# series_parallel_examples4.net
KiCad netlist of a schematic drawn in EAGLE
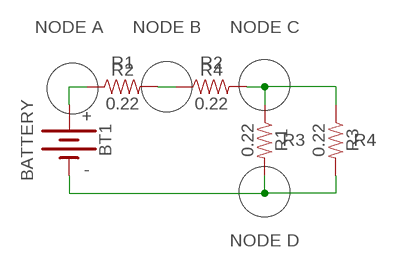
[diagram p0: schematic, sheet 1]

(export (version "E")
  (design (tool "Eeschema 10.0.6"))
  (components
    (comp (ref "BT1")
      (value "BATTERY-9V")
      (footprint "eagle-import:BATTCON_9V")
      (libsource (lib "eagle-import") (part "BATTERY-9V"))
    )
    (comp (ref "R1")
      (value "0.22")
      (footprint "eagle-import:0805")
      (libsource (lib "eagle-import") (part "0.22OHM-0805-1/4W-1%"))
    )
    (comp (ref "R2")
      (value "0.22")
      (footprint "eagle-import:0805")
      (libsource (lib "eagle-import") (part "0.22OHM-0805-1/4W-1%"))
    )
    (comp (ref "R3")
      (value "0.22")
      (footprint "eagle-import:0805")
      (libsource (lib "eagle-import") (part "0.22OHM-0805-1/4W-1%"))
    )
    (comp (ref "R4")
      (value "0.22")
      (footprint "eagle-import:0805")
      (libsource (lib "eagle-import") (part "0.22OHM-0805-1/4W-1%"))
    )
  )
  (nets
    (net (code "1") (name "Net-(BT1-Pad+)") (class "Default")
      (node (ref "BT1") (pin "+") (pinfunction "+_+") (pintype "power_in"))
      (node (ref "R2") (pin "1") (pinfunction "1_1") (pintype "passive"))
    )
    (net (code "2") (name "Net-(BT1-Pad-)") (class "Default")
      (node (ref "BT1") (pin "-") (pinfunction "-_-") (pintype "power_in"))
      (node (ref "R1") (pin "2") (pinfunction "2_2") (pintype "passive"))
      (node (ref "R3") (pin "2") (pinfunction "2_2") (pintype "passive"))
    )
    (net (code "3") (name "Net-(R1-Pad1)") (class "Default")
      (node (ref "R1") (pin "1") (pinfunction "1_1") (pintype "passive"))
      (node (ref "R3") (pin "1") (pinfunction "1_1") (pintype "passive"))
      (node (ref "R4") (pin "2") (pinfunction "2_2") (pintype "passive"))
    )
    (net (code "4") (name "Net-(R2-Pad2)") (class "Default")
      (node (ref "R2") (pin "2") (pinfunction "2_2") (pintype "passive"))
      (node (ref "R4") (pin "1") (pinfunction "1_1") (pintype "passive"))
    )
  )
)
